# Sheet1.net
KiCad netlist of a schematic drawn in Altium Designer
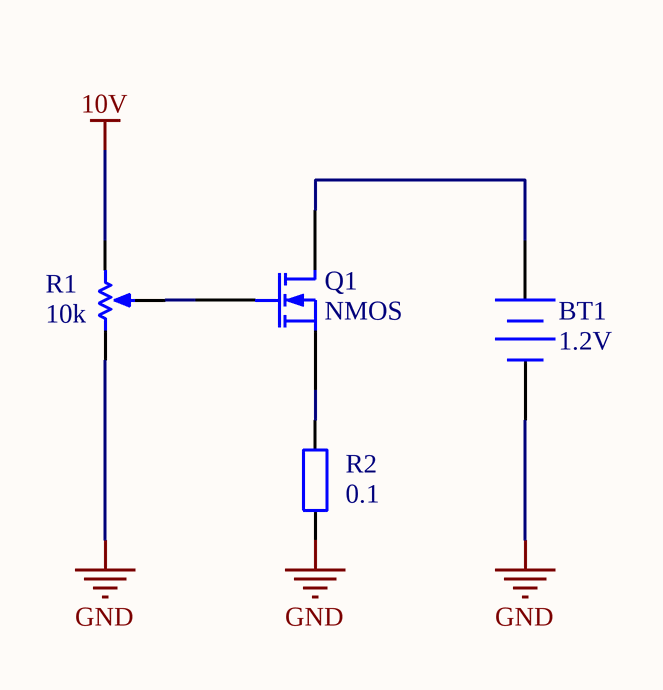
[diagram p0: Sheet1.SchDoc]

(export (version "E")
  (design (tool "Eeschema 10.0.6"))
  (components
    (comp (ref "BT1")
      (value "1.2V")
      (footprint "BAT-2")
      (description "Multicell Battery")
      (fields (field (name "PUBLISHER") "Altium Limited"))
      (libsource (lib "Miscellaneous Devices") (part "Battery"))
    )
    (comp (ref "Q1")
      (value "NMOS")
      (footprint "E3")
      (description "N-Channel MOSFET")
      (fields (field (name "PUBLISHER") "Altium Limited"))
      (libsource (lib "Miscellaneous Devices") (part "MOSFET-N"))
    )
    (comp (ref "R1")
      (value "10k")
      (footprint "VR5")
      (description "Potentiometer")
      (fields (field (name "Comment") "RPot") (field (name "PUBLISHER") "Altium Limited"))
      (libsource (lib "Miscellaneous Devices") (part "RPot"))
    )
    (comp (ref "R2")
      (value "0.1")
      (footprint "AXIAL-0.4")
      (description "Resistor")
      (fields (field (name "PUBLISHER") "Altium Limited"))
      (libsource (lib "Miscellaneous Devices") (part "Res2"))
    )
  )
  (nets
    (net (code "1") (name "10V") (class "Default")
      (node (ref "R1") (pin "2") (pinfunction "BOT_2") (pintype "passive"))
    )
    (net (code "2") (name "GND") (class "Default")
      (node (ref "BT1") (pin "2") (pinfunction "-_2") (pintype "passive"))
      (node (ref "R1") (pin "1") (pinfunction "TOP_1") (pintype "passive"))
      (node (ref "R2") (pin "1") (pinfunction "1_1") (pintype "passive"))
    )
    (net (code "3") (name "Net-(BT1-+)") (class "Default")
      (node (ref "BT1") (pin "1") (pinfunction "+_1") (pintype "passive"))
      (node (ref "Q1") (pin "1") (pinfunction "D_1") (pintype "passive"))
    )
    (net (code "4") (name "Net-(Q1-G)") (class "Default")
      (node (ref "Q1") (pin "2") (pinfunction "G_2") (pintype "passive"))
      (node (ref "R1") (pin "3") (pinfunction "TAP_3") (pintype "passive"))
    )
    (net (code "5") (name "Net-(Q1-S)") (class "Default")
      (node (ref "Q1") (pin "3") (pinfunction "S_3") (pintype "passive"))
      (node (ref "R2") (pin "2") (pinfunction "2_2") (pintype "passive"))
    )
  )
)
